# Tester.net
KiCad netlist of a schematic drawn in EAGLE
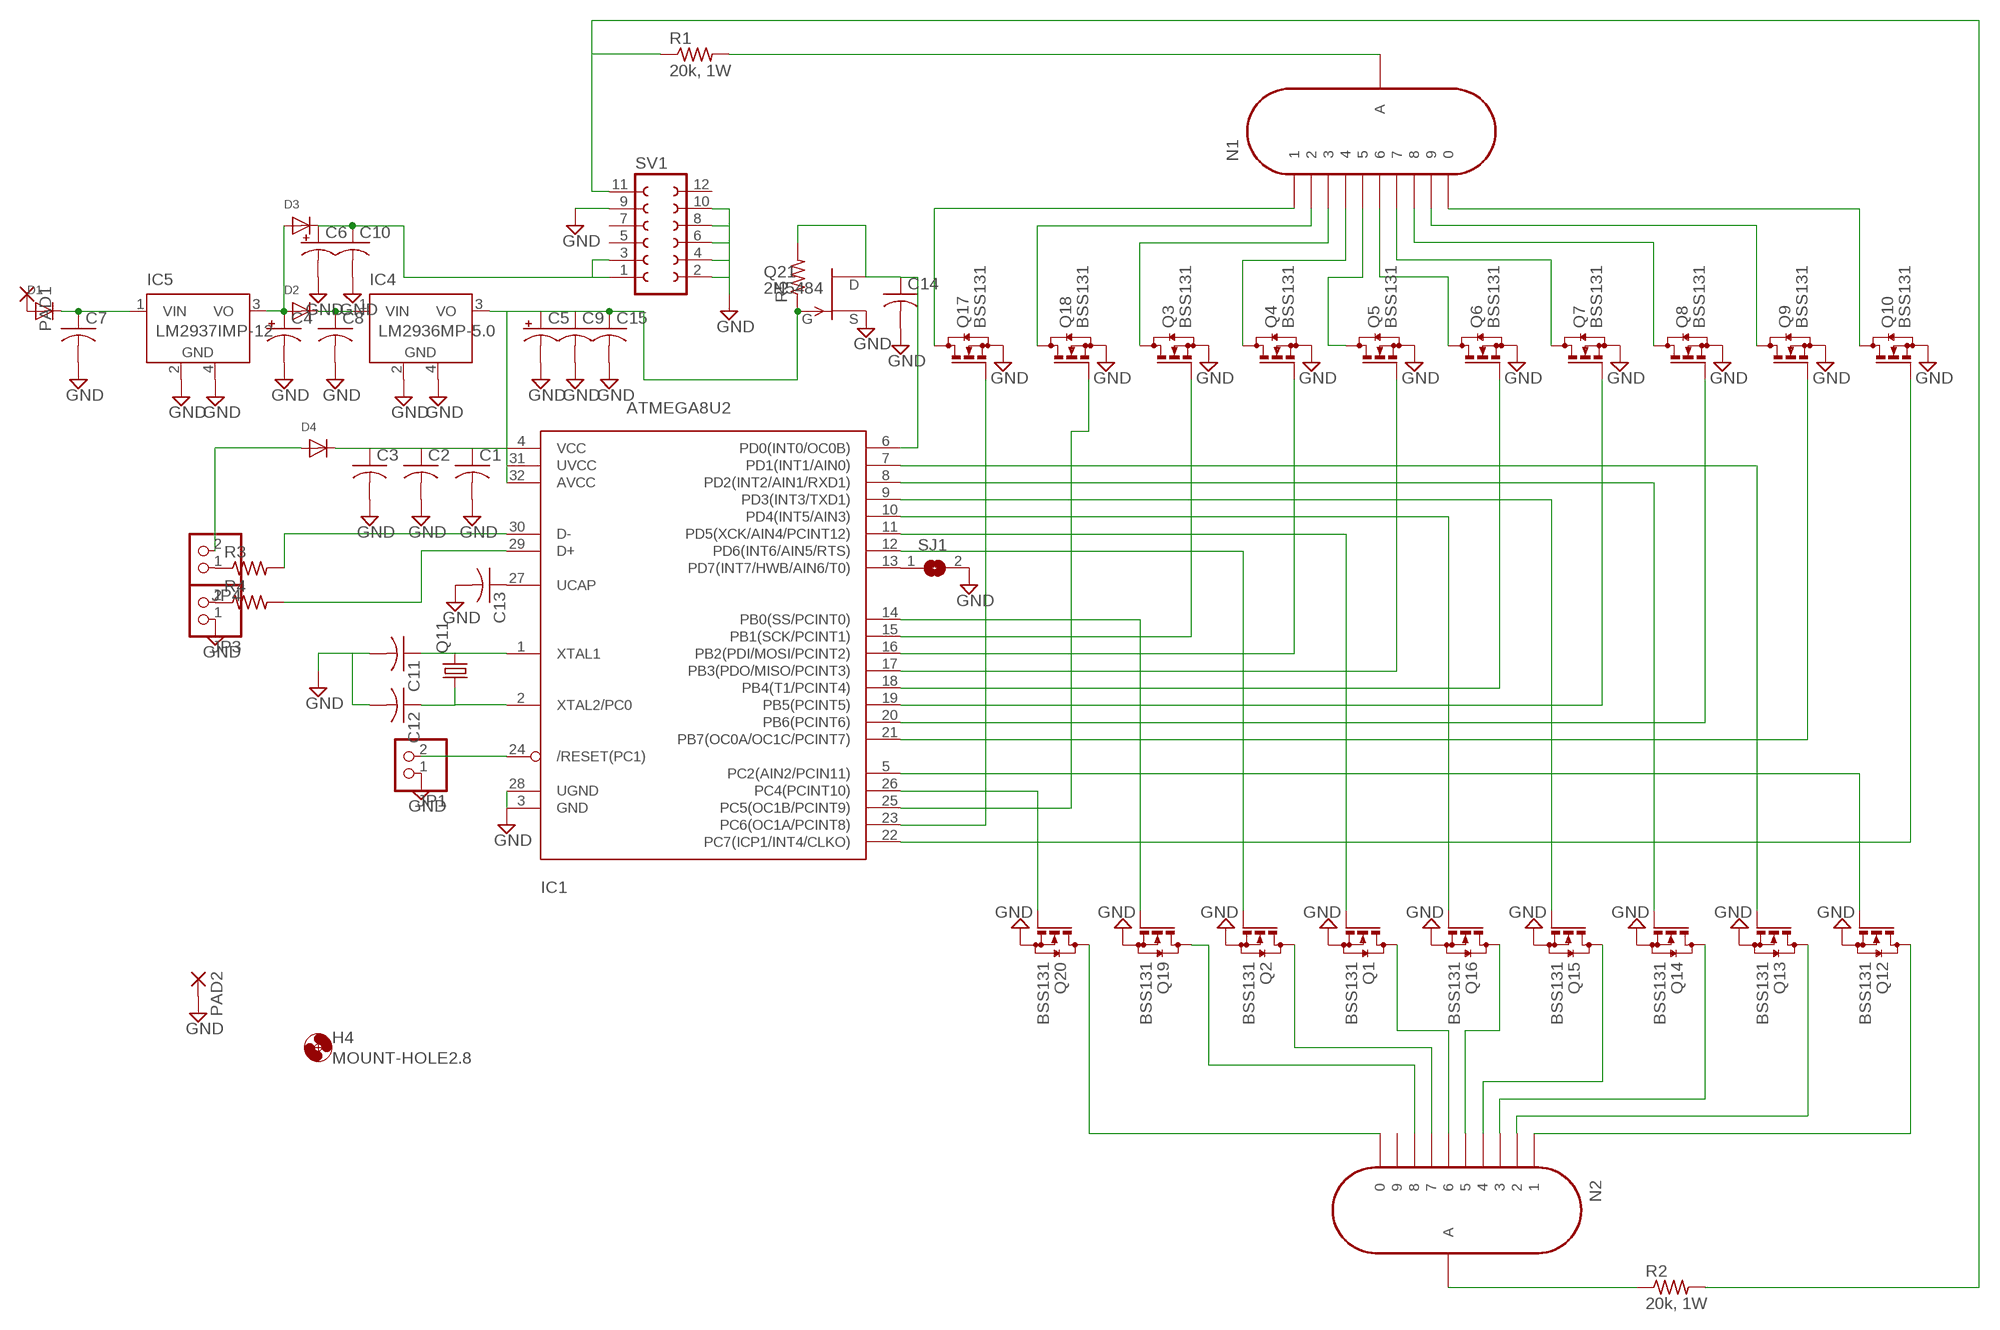
[diagram p0: schematic, sheet 1]

(export (version "E")
  (design (tool "Eeschema 10.0.6"))
  (components
    (comp (ref "C1")
      (value "C-USC0603K")
      (footprint "eagle-import:C0603K")
      (libsource (lib "eagle-import") (part "C-USC0603K"))
    )
    (comp (ref "C2")
      (value "C-USC0603K")
      (footprint "eagle-import:C0603K")
      (libsource (lib "eagle-import") (part "C-USC0603K"))
    )
    (comp (ref "C3")
      (value "C-USC0603K")
      (footprint "eagle-import:C0603K")
      (libsource (lib "eagle-import") (part "C-USC0603K"))
    )
    (comp (ref "C4")
      (value "CPOL-USE3.5-8")
      (footprint "eagle-import:E3,5-8")
      (libsource (lib "eagle-import") (part "CPOL-USE3.5-8"))
    )
    (comp (ref "C5")
      (value "CPOL-USE3.5-8")
      (footprint "eagle-import:E3,5-8")
      (libsource (lib "eagle-import") (part "CPOL-USE3.5-8"))
    )
    (comp (ref "C6")
      (value "CPOL-USE3.5-8")
      (footprint "eagle-import:E3,5-8")
      (libsource (lib "eagle-import") (part "CPOL-USE3.5-8"))
    )
    (comp (ref "C7")
      (value "C-USC1206K")
      (footprint "eagle-import:C1206K")
      (libsource (lib "eagle-import") (part "C-USC1206K"))
    )
    (comp (ref "C8")
      (value "C-USC1206K")
      (footprint "eagle-import:C1206K")
      (libsource (lib "eagle-import") (part "C-USC1206K"))
    )
    (comp (ref "C9")
      (value "C-USC1206K")
      (footprint "eagle-import:C1206K")
      (libsource (lib "eagle-import") (part "C-USC1206K"))
    )
    (comp (ref "C10")
      (value "C-USC1206K")
      (footprint "eagle-import:C1206K")
      (libsource (lib "eagle-import") (part "C-USC1206K"))
    )
    (comp (ref "C11")
      (value "C-USC1206K")
      (footprint "eagle-import:C1206K")
      (libsource (lib "eagle-import") (part "C-USC1206K"))
    )
    (comp (ref "C12")
      (value "C-USC1206K")
      (footprint "eagle-import:C1206K")
      (libsource (lib "eagle-import") (part "C-USC1206K"))
    )
    (comp (ref "C13")
      (value "C-USC1206K")
      (footprint "eagle-import:C1206K")
      (libsource (lib "eagle-import") (part "C-USC1206K"))
    )
    (comp (ref "C14")
      (value "C-USC1206K")
      (footprint "eagle-import:C1206K")
      (libsource (lib "eagle-import") (part "C-USC1206K"))
    )
    (comp (ref "C15")
      (value "C-USC1206K")
      (footprint "eagle-import:C1206K")
      (libsource (lib "eagle-import") (part "C-USC1206K"))
    )
    (comp (ref "D1")
      (value "DIODESMA")
      (footprint "eagle-import:SMADIODE")
      (libsource (lib "eagle-import") (part "DIODESMA"))
    )
    (comp (ref "D2")
      (value "DIODESMA")
      (footprint "eagle-import:SMADIODE")
      (libsource (lib "eagle-import") (part "DIODESMA"))
    )
    (comp (ref "D3")
      (value "DIODESMA")
      (footprint "eagle-import:SMADIODE")
      (libsource (lib "eagle-import") (part "DIODESMA"))
    )
    (comp (ref "D4")
      (value "DIODESOD-123")
      (footprint "eagle-import:SOD-123")
      (libsource (lib "eagle-import") (part "DIODESOD-123"))
    )
    (comp (ref "H4")
      (value "MOUNT-HOLE2.8")
      (footprint "eagle-import:2,8")
      (libsource (lib "eagle-import") (part "MOUNT-HOLE2.8"))
    )
    (comp (ref "IC1")
      (value "ATMEGA8U2")
      (footprint "eagle-import:TQFP32-08")
      (libsource (lib "eagle-import") (part "ATMEGA32U2-TQFP"))
    )
    (comp (ref "IC4")
      (value "LM2936MP-5.0")
      (footprint "eagle-import:SOT223")
      (fields (field (name "MF") "NATIONAL SEMICONDUCTOR") (field (name "MPN") "LM2936MP-5.0/NOPB"))
      (libsource (lib "eagle-import") (part "LM2936MP?-5.0"))
    )
    (comp (ref "IC5")
      (value "LM2937IMP-12")
      (footprint "eagle-import:SOT223")
      (fields (field (name "MF") "NATIONAL SEMICONDUCTOR") (field (name "MPN") "LM2936MP-5.0/NOPB"))
      (libsource (lib "eagle-import") (part "LM2936MP?-5.0"))
    )
    (comp (ref "JP1")
      (value "PINHD-1X2")
      (footprint "eagle-import:1X02")
      (libsource (lib "eagle-import") (part "PINHD-1X2"))
    )
    (comp (ref "JP3")
      (value "PINHD-1X2")
      (footprint "eagle-import:1X02")
      (libsource (lib "eagle-import") (part "PINHD-1X2"))
    )
    (comp (ref "JP4")
      (value "PINHD-1X2")
      (footprint "eagle-import:1X02")
      (libsource (lib "eagle-import") (part "PINHD-1X2"))
    )
    (comp (ref "N1")
      (value "IN-12A")
      (footprint "eagle-import:IN-12")
      (libsource (lib "eagle-import") (part "IN-12A"))
    )
    (comp (ref "N2")
      (value "IN-12A")
      (footprint "eagle-import:IN-12")
      (libsource (lib "eagle-import") (part "IN-12A"))
    )
    (comp (ref "PAD1")
      (value "3,81/1,4")
      (footprint "eagle-import:3,81_1,4")
      (libsource (lib "eagle-import") (part "3,81/1,4"))
    )
    (comp (ref "PAD2")
      (value "3,81/1,4")
      (footprint "eagle-import:3,81_1,4")
      (libsource (lib "eagle-import") (part "3,81/1,4"))
    )
    (comp (ref "Q1")
      (value "BSS131")
      (footprint "eagle-import:SOT23")
      (libsource (lib "eagle-import") (part "BSS123"))
    )
    (comp (ref "Q2")
      (value "BSS131")
      (footprint "eagle-import:SOT23")
      (libsource (lib "eagle-import") (part "BSS123"))
    )
    (comp (ref "Q3")
      (value "BSS131")
      (footprint "eagle-import:SOT23")
      (libsource (lib "eagle-import") (part "BSS123"))
    )
    (comp (ref "Q4")
      (value "BSS131")
      (footprint "eagle-import:SOT23")
      (libsource (lib "eagle-import") (part "BSS123"))
    )
    (comp (ref "Q5")
      (value "BSS131")
      (footprint "eagle-import:SOT23")
      (libsource (lib "eagle-import") (part "BSS123"))
    )
    (comp (ref "Q6")
      (value "BSS131")
      (footprint "eagle-import:SOT23")
      (libsource (lib "eagle-import") (part "BSS123"))
    )
    (comp (ref "Q7")
      (value "BSS131")
      (footprint "eagle-import:SOT23")
      (libsource (lib "eagle-import") (part "BSS123"))
    )
    (comp (ref "Q8")
      (value "BSS131")
      (footprint "eagle-import:SOT23")
      (libsource (lib "eagle-import") (part "BSS123"))
    )
    (comp (ref "Q9")
      (value "BSS131")
      (footprint "eagle-import:SOT23")
      (libsource (lib "eagle-import") (part "BSS123"))
    )
    (comp (ref "Q10")
      (value "BSS131")
      (footprint "eagle-import:SOT23")
      (libsource (lib "eagle-import") (part "BSS123"))
    )
    (comp (ref "Q11")
      (value "CRYSTALHC49S")
      (footprint "eagle-import:HC49_S")
      (libsource (lib "eagle-import") (part "CRYSTALHC49S"))
    )
    (comp (ref "Q12")
      (value "BSS131")
      (footprint "eagle-import:SOT23")
      (libsource (lib "eagle-import") (part "BSS123"))
    )
    (comp (ref "Q13")
      (value "BSS131")
      (footprint "eagle-import:SOT23")
      (libsource (lib "eagle-import") (part "BSS123"))
    )
    (comp (ref "Q14")
      (value "BSS131")
      (footprint "eagle-import:SOT23")
      (libsource (lib "eagle-import") (part "BSS123"))
    )
    (comp (ref "Q15")
      (value "BSS131")
      (footprint "eagle-import:SOT23")
      (libsource (lib "eagle-import") (part "BSS123"))
    )
    (comp (ref "Q16")
      (value "BSS131")
      (footprint "eagle-import:SOT23")
      (libsource (lib "eagle-import") (part "BSS123"))
    )
    (comp (ref "Q17")
      (value "BSS131")
      (footprint "eagle-import:SOT23")
      (libsource (lib "eagle-import") (part "BSS123"))
    )
    (comp (ref "Q18")
      (value "BSS131")
      (footprint "eagle-import:SOT23")
      (libsource (lib "eagle-import") (part "BSS123"))
    )
    (comp (ref "Q19")
      (value "BSS131")
      (footprint "eagle-import:SOT23")
      (libsource (lib "eagle-import") (part "BSS123"))
    )
    (comp (ref "Q20")
      (value "BSS131")
      (footprint "eagle-import:SOT23")
      (libsource (lib "eagle-import") (part "BSS123"))
    )
    (comp (ref "Q21")
      (value "2N5484")
      (footprint "eagle-import:TO92-")
      (libsource (lib "eagle-import") (part "?5482N4"))
    )
    (comp (ref "R1")
      (value "20k, 1W")
      (footprint "eagle-import:0309_12")
      (libsource (lib "eagle-import") (part "resistor_R-US_0309/12"))
    )
    (comp (ref "R2")
      (value "20k, 1W")
      (footprint "eagle-import:0309V")
      (libsource (lib "eagle-import") (part "resistor_R-US_0309/V"))
    )
    (comp (ref "R3")
      (value "R-US_R0805")
      (footprint "eagle-import:R0805")
      (libsource (lib "eagle-import") (part "R-US_R0805"))
    )
    (comp (ref "R4")
      (value "R-US_R0805")
      (footprint "eagle-import:R0805")
      (libsource (lib "eagle-import") (part "R-US_R0805"))
    )
    (comp (ref "R5")
      (value "R-US_R0805")
      (footprint "eagle-import:R0805")
      (libsource (lib "eagle-import") (part "R-US_R0805"))
    )
    (comp (ref "SJ1") (value "SJ") (footprint "eagle-import:SJ") (libsource (lib "eagle-import") (part "SJ")))
    (comp (ref "SV1")
      (value "FE06-2")
      (footprint "eagle-import:FE06-2")
      (libsource (lib "eagle-import") (part "FE06-2"))
    )
  )
  (nets
    (net (code "1") (name "GND") (class "Default")
      (node (ref "C1") (pin "2") (pinfunction "2_2") (pintype "passive"))
      (node (ref "C10") (pin "2") (pinfunction "2_2") (pintype "passive"))
      (node (ref "C11") (pin "2") (pinfunction "2_2") (pintype "passive"))
      (node (ref "C12") (pin "2") (pinfunction "2_2") (pintype "passive"))
      (node (ref "C13") (pin "2") (pinfunction "2_2") (pintype "passive"))
      (node (ref "C14") (pin "2") (pinfunction "2_2") (pintype "passive"))
      (node (ref "C15") (pin "2") (pinfunction "2_2") (pintype "passive"))
      (node (ref "C2") (pin "2") (pinfunction "2_2") (pintype "passive"))
      (node (ref "C3") (pin "2") (pinfunction "2_2") (pintype "passive"))
      (node (ref "C4") (pin "-") (pinfunction "-_-") (pintype "passive"))
      (node (ref "C5") (pin "-") (pinfunction "-_-") (pintype "passive"))
      (node (ref "C6") (pin "-") (pinfunction "-_-") (pintype "passive"))
      (node (ref "C7") (pin "2") (pinfunction "2_2") (pintype "passive"))
      (node (ref "C8") (pin "2") (pinfunction "2_2") (pintype "passive"))
      (node (ref "C9") (pin "2") (pinfunction "2_2") (pintype "passive"))
      (node (ref "IC1") (pin "28") (pinfunction "UGND_28") (pintype "bidirectional"))
      (node (ref "IC1") (pin "3") (pinfunction "GND_3") (pintype "bidirectional"))
      (node (ref "IC4") (pin "2") (pinfunction "GND_2") (pintype "passive"))
      (node (ref "IC4") (pin "4") (pinfunction "GND_4") (pintype "passive"))
      (node (ref "IC5") (pin "2") (pinfunction "GND_2") (pintype "passive"))
      (node (ref "IC5") (pin "4") (pinfunction "GND_4") (pintype "passive"))
      (node (ref "JP1") (pin "1") (pinfunction "1_1") (pintype "passive"))
      (node (ref "JP3") (pin "1") (pinfunction "1_1") (pintype "passive"))
      (node (ref "PAD2") (pin "1") (pinfunction "P_1") (pintype "passive"))
      (node (ref "Q1") (pin "2") (pinfunction "S_2") (pintype "passive"))
      (node (ref "Q10") (pin "2") (pinfunction "S_2") (pintype "passive"))
      (node (ref "Q12") (pin "2") (pinfunction "S_2") (pintype "passive"))
      (node (ref "Q13") (pin "2") (pinfunction "S_2") (pintype "passive"))
      (node (ref "Q14") (pin "2") (pinfunction "S_2") (pintype "passive"))
      (node (ref "Q15") (pin "2") (pinfunction "S_2") (pintype "passive"))
      (node (ref "Q16") (pin "2") (pinfunction "S_2") (pintype "passive"))
      (node (ref "Q17") (pin "2") (pinfunction "S_2") (pintype "passive"))
      (node (ref "Q18") (pin "2") (pinfunction "S_2") (pintype "passive"))
      (node (ref "Q19") (pin "2") (pinfunction "S_2") (pintype "passive"))
      (node (ref "Q2") (pin "2") (pinfunction "S_2") (pintype "passive"))
      (node (ref "Q20") (pin "2") (pinfunction "S_2") (pintype "passive"))
      (node (ref "Q21") (pin "2") (pinfunction "S_2") (pintype "passive"))
      (node (ref "Q3") (pin "2") (pinfunction "S_2") (pintype "passive"))
      (node (ref "Q4") (pin "2") (pinfunction "S_2") (pintype "passive"))
      (node (ref "Q5") (pin "2") (pinfunction "S_2") (pintype "passive"))
      (node (ref "Q6") (pin "2") (pinfunction "S_2") (pintype "passive"))
      (node (ref "Q7") (pin "2") (pinfunction "S_2") (pintype "passive"))
      (node (ref "Q8") (pin "2") (pinfunction "S_2") (pintype "passive"))
      (node (ref "Q9") (pin "2") (pinfunction "S_2") (pintype "passive"))
      (node (ref "SJ1") (pin "2") (pinfunction "2_2") (pintype "passive"))
      (node (ref "SV1") (pin "10") (pinfunction "10_10") (pintype "passive"))
      (node (ref "SV1") (pin "2") (pinfunction "2_2") (pintype "passive"))
      (node (ref "SV1") (pin "4") (pinfunction "4_4") (pintype "passive"))
      (node (ref "SV1") (pin "6") (pinfunction "6_6") (pintype "passive"))
      (node (ref "SV1") (pin "8") (pinfunction "8_8") (pintype "passive"))
      (node (ref "SV1") (pin "9") (pinfunction "9_9") (pintype "passive"))
    )
    (net (code "2") (name "Net-(C10-Pad1)") (class "Default")
      (node (ref "C10") (pin "1") (pinfunction "1_1") (pintype "passive"))
      (node (ref "C6") (pin "+") (pinfunction "+_+") (pintype "passive"))
      (node (ref "D3") (pin "C") (pinfunction "C_C") (pintype "passive"))
      (node (ref "SV1") (pin "1") (pinfunction "1_1") (pintype "passive"))
      (node (ref "SV1") (pin "3") (pinfunction "3_3") (pintype "passive"))
    )
    (net (code "3") (name "Net-(D4-PadA)") (class "Default")
      (node (ref "D4") (pin "A") (pinfunction "A_A") (pintype "passive"))
      (node (ref "JP4") (pin "2") (pinfunction "2_2") (pintype "passive"))
    )
    (net (code "4") (name "Net-(IC1-AVCC)") (class "Default")
      (node (ref "C1") (pin "1") (pinfunction "1_1") (pintype "passive"))
      (node (ref "C15") (pin "1") (pinfunction "1_1") (pintype "passive"))
      (node (ref "C2") (pin "1") (pinfunction "1_1") (pintype "passive"))
      (node (ref "C3") (pin "1") (pinfunction "1_1") (pintype "passive"))
      (node (ref "C5") (pin "+") (pinfunction "+_+") (pintype "passive"))
      (node (ref "C9") (pin "1") (pinfunction "1_1") (pintype "passive"))
      (node (ref "D4") (pin "C") (pinfunction "C_C") (pintype "passive"))
      (node (ref "IC1") (pin "31") (pinfunction "UVCC_31") (pintype "bidirectional"))
      (node (ref "IC1") (pin "32") (pinfunction "AVCC_32") (pintype "bidirectional"))
      (node (ref "IC1") (pin "4") (pinfunction "VCC_4") (pintype "bidirectional"))
      (node (ref "IC4") (pin "3") (pinfunction "VO_3") (pintype "passive"))
      (node (ref "Q21") (pin "1") (pinfunction "G_1") (pintype "passive"))
      (node (ref "R5") (pin "1") (pinfunction "1_1") (pintype "passive"))
    )
    (net (code "5") (name "Net-(IC1-D+)") (class "Default")
      (node (ref "IC1") (pin "29") (pinfunction "D+_29") (pintype "bidirectional"))
      (node (ref "R4") (pin "2") (pinfunction "2_2") (pintype "passive"))
    )
    (net (code "6") (name "Net-(IC1-D-)") (class "Default")
      (node (ref "IC1") (pin "30") (pinfunction "D-_30") (pintype "bidirectional"))
      (node (ref "R3") (pin "2") (pinfunction "2_2") (pintype "passive"))
    )
    (net (code "7") (name "Net-(IC1-PB0(SS{slash}PCINT0))") (class "Default")
      (node (ref "IC1") (pin "14") (pinfunction "PB0(SS/PCINT0)_14") (pintype "bidirectional"))
      (node (ref "Q19") (pin "1") (pinfunction "G_1") (pintype "passive"))
    )
    (net (code "8") (name "Net-(IC1-PB1(SCK{slash}PCINT1))") (class "Default")
      (node (ref "IC1") (pin "15") (pinfunction "PB1(SCK/PCINT1)_15") (pintype "bidirectional"))
      (node (ref "Q3") (pin "1") (pinfunction "G_1") (pintype "passive"))
    )
    (net (code "9") (name "Net-(IC1-PB2(PDI{slash}MOSI{slash}PCINT2))") (class "Default")
      (node (ref "IC1") (pin "16") (pinfunction "PB2(PDI/MOSI/PCINT2)_16") (pintype "bidirectional"))
      (node (ref "Q4") (pin "1") (pinfunction "G_1") (pintype "passive"))
    )
    (net (code "10") (name "Net-(IC1-PB3(PDO{slash}MISO{slash}PCINT3))") (class "Default")
      (node (ref "IC1") (pin "17") (pinfunction "PB3(PDO/MISO/PCINT3)_17") (pintype "bidirectional"))
      (node (ref "Q5") (pin "1") (pinfunction "G_1") (pintype "passive"))
    )
    (net (code "11") (name "Net-(IC1-PB4(T1{slash}PCINT4))") (class "Default")
      (node (ref "IC1") (pin "18") (pinfunction "PB4(T1/PCINT4)_18") (pintype "bidirectional"))
      (node (ref "Q6") (pin "1") (pinfunction "G_1") (pintype "passive"))
    )
    (net (code "12") (name "Net-(IC1-PB5(PCINT5))") (class "Default")
      (node (ref "IC1") (pin "19") (pinfunction "PB5(PCINT5)_19") (pintype "bidirectional"))
      (node (ref "Q7") (pin "1") (pinfunction "G_1") (pintype "passive"))
    )
    (net (code "13") (name "Net-(IC1-PB6(PCINT6))") (class "Default")
      (node (ref "IC1") (pin "20") (pinfunction "PB6(PCINT6)_20") (pintype "bidirectional"))
      (node (ref "Q8") (pin "1") (pinfunction "G_1") (pintype "passive"))
    )
    (net (code "14") (name "Net-(IC1-PB7(OC0A{slash}OC1C{slash}PCINT7))") (class "Default")
      (node (ref "IC1") (pin "21") (pinfunction "PB7(OC0A/OC1C/PCINT7)_21") (pintype "bidirectional"))
      (node (ref "Q9") (pin "1") (pinfunction "G_1") (pintype "passive"))
    )
    (net (code "15") (name "Net-(IC1-PC2(AIN2{slash}PCIN11))") (class "Default")
      (node (ref "IC1") (pin "5") (pinfunction "PC2(AIN2/PCIN11)_5") (pintype "bidirectional"))
      (node (ref "Q12") (pin "1") (pinfunction "G_1") (pintype "passive"))
    )
    (net (code "16") (name "Net-(IC1-PC4(PCINT10))") (class "Default")
      (node (ref "IC1") (pin "26") (pinfunction "PC4(PCINT10)_26") (pintype "bidirectional"))
      (node (ref "Q20") (pin "1") (pinfunction "G_1") (pintype "passive"))
    )
    (net (code "17") (name "Net-(IC1-PC5(OC1B{slash}PCINT9))") (class "Default")
      (node (ref "IC1") (pin "25") (pinfunction "PC5(OC1B/PCINT9)_25") (pintype "bidirectional"))
      (node (ref "Q18") (pin "1") (pinfunction "G_1") (pintype "passive"))
    )
    (net (code "18") (name "Net-(IC1-PC6(OC1A{slash}PCINT8))") (class "Default")
      (node (ref "IC1") (pin "23") (pinfunction "PC6(OC1A/PCINT8)_23") (pintype "bidirectional"))
      (node (ref "Q17") (pin "1") (pinfunction "G_1") (pintype "passive"))
    )
    (net (code "19") (name "Net-(IC1-PC7(ICP1{slash}INT4{slash}CLKO))") (class "Default")
      (node (ref "IC1") (pin "22") (pinfunction "PC7(ICP1/INT4/CLKO)_22") (pintype "bidirectional"))
      (node (ref "Q10") (pin "1") (pinfunction "G_1") (pintype "passive"))
    )
    (net (code "20") (name "Net-(IC1-PD0(INT0{slash}OC0B))") (class "Default")
      (node (ref "C14") (pin "1") (pinfunction "1_1") (pintype "passive"))
      (node (ref "IC1") (pin "6") (pinfunction "PD0(INT0/OC0B)_6") (pintype "bidirectional"))
      (node (ref "Q21") (pin "3") (pinfunction "D_3") (pintype "passive"))
      (node (ref "R5") (pin "2") (pinfunction "2_2") (pintype "passive"))
    )
    (net (code "21") (name "Net-(IC1-PD1(INT1{slash}AIN0))") (class "Default")
      (node (ref "IC1") (pin "7") (pinfunction "PD1(INT1/AIN0)_7") (pintype "bidirectional"))
      (node (ref "Q13") (pin "1") (pinfunction "G_1") (pintype "passive"))
    )
    (net (code "22") (name "Net-(IC1-PD2(INT2{slash}AIN1{slash}RXD1))") (class "Default")
      (node (ref "IC1") (pin "8") (pinfunction "PD2(INT2/AIN1/RXD1)_8") (pintype "bidirectional"))
      (node (ref "Q14") (pin "1") (pinfunction "G_1") (pintype "passive"))
    )
    (net (code "23") (name "Net-(IC1-PD3(INT3{slash}TXD1))") (class "Default")
      (node (ref "IC1") (pin "9") (pinfunction "PD3(INT3/TXD1)_9") (pintype "bidirectional"))
      (node (ref "Q15") (pin "1") (pinfunction "G_1") (pintype "passive"))
    )
    (net (code "24") (name "Net-(IC1-PD4(INT5{slash}AIN3))") (class "Default")
      (node (ref "IC1") (pin "10") (pinfunction "PD4(INT5/AIN3)_10") (pintype "bidirectional"))
      (node (ref "Q16") (pin "1") (pinfunction "G_1") (pintype "passive"))
    )
    (net (code "25") (name "Net-(IC1-PD5(XCK{slash}AIN4{slash}PCINT12))") (class "Default")
      (node (ref "IC1") (pin "11") (pinfunction "PD5(XCK/AIN4/PCINT12)_11") (pintype "bidirectional"))
      (node (ref "Q1") (pin "1") (pinfunction "G_1") (pintype "passive"))
    )
    (net (code "26") (name "Net-(IC1-PD6(INT6{slash}AIN5{slash}RTS))") (class "Default")
      (node (ref "IC1") (pin "12") (pinfunction "PD6(INT6/AIN5/RTS)_12") (pintype "bidirectional"))
      (node (ref "Q2") (pin "1") (pinfunction "G_1") (pintype "passive"))
    )
    (net (code "27") (name "Net-(IC1-PD7(INT7{slash}HWB{slash}AIN6{slash}T0))") (class "Default")
      (node (ref "IC1") (pin "13") (pinfunction "PD7(INT7/HWB/AIN6/T0)_13") (pintype "bidirectional"))
      (node (ref "SJ1") (pin "1") (pinfunction "1_1") (pintype "passive"))
    )
    (net (code "28") (name "Net-(IC1-UCAP)") (class "Default")
      (node (ref "C13") (pin "1") (pinfunction "1_1") (pintype "passive"))
      (node (ref "IC1") (pin "27") (pinfunction "UCAP_27") (pintype "bidirectional"))
    )
    (net (code "29") (name "Net-(IC1-XTAL1)") (class "Default")
      (node (ref "C11") (pin "1") (pinfunction "1_1") (pintype "passive"))
      (node (ref "IC1") (pin "1") (pinfunction "XTAL1_1") (pintype "bidirectional"))
      (node (ref "Q11") (pin "2") (pinfunction "2_2") (pintype "passive"))
    )
    (net (code "30") (name "Net-(IC1-XTAL2{slash}PC0)") (class "Default")
      (node (ref "C12") (pin "1") (pinfunction "1_1") (pintype "passive"))
      (node (ref "IC1") (pin "2") (pinfunction "XTAL2/PC0_2") (pintype "bidirectional"))
      (node (ref "Q11") (pin "1") (pinfunction "1_1") (pintype "passive"))
    )
    (net (code "31") (name "Net-(IC1-{slash}RESET(PC1))") (class "Default")
      (node (ref "IC1") (pin "24") (pinfunction "/RESET(PC1)_24") (pintype "bidirectional"))
      (node (ref "JP1") (pin "2") (pinfunction "2_2") (pintype "passive"))
    )
    (net (code "32") (name "Net-(IC4-VIN)") (class "Default")
      (node (ref "C8") (pin "1") (pinfunction "1_1") (pintype "passive"))
      (node (ref "D2") (pin "C") (pinfunction "C_C") (pintype "passive"))
      (node (ref "IC4") (pin "1") (pinfunction "VIN_1") (pintype "input"))
    )
    (net (code "33") (name "Net-(IC5-VIN)") (class "Default")
      (node (ref "C7") (pin "1") (pinfunction "1_1") (pintype "passive"))
      (node (ref "D1") (pin "C") (pinfunction "C_C") (pintype "passive"))
      (node (ref "IC5") (pin "1") (pinfunction "VIN_1") (pintype "input"))
    )
    (net (code "34") (name "Net-(IC5-VO)") (class "Default")
      (node (ref "C4") (pin "+") (pinfunction "+_+") (pintype "passive"))
      (node (ref "D2") (pin "A") (pinfunction "A_A") (pintype "passive"))
      (node (ref "D3") (pin "A") (pinfunction "A_A") (pintype "passive"))
      (node (ref "IC5") (pin "3") (pinfunction "VO_3") (pintype "passive"))
    )
    (net (code "35") (name "Net-(JP3-Pad2)") (class "Default")
      (node (ref "JP3") (pin "2") (pinfunction "2_2") (pintype "passive"))
      (node (ref "R4") (pin "1") (pinfunction "1_1") (pintype "passive"))
    )
    (net (code "36") (name "Net-(JP4-Pad1)") (class "Default")
      (node (ref "JP4") (pin "1") (pinfunction "1_1") (pintype "passive"))
      (node (ref "R3") (pin "1") (pinfunction "1_1") (pintype "passive"))
    )
    (net (code "37") (name "Net-(N1-PadA)") (class "Default")
      (node (ref "N1") (pin "A") (pinfunction "A_A") (pintype "bidirectional"))
      (node (ref "R1") (pin "2") (pinfunction "2_2") (pintype "passive"))
    )
    (net (code "38") (name "Net-(N2-PadA)") (class "Default")
      (node (ref "N2") (pin "A") (pinfunction "A_A") (pintype "bidirectional"))
      (node (ref "R2") (pin "1") (pinfunction "1_1") (pintype "passive"))
    )
    (net (code "39") (name "Net-(PAD1-P)") (class "Default")
      (node (ref "D1") (pin "A") (pinfunction "A_A") (pintype "passive"))
      (node (ref "PAD1") (pin "1") (pinfunction "P_1") (pintype "passive"))
    )
    (net (code "40") (name "Net-(Q1-D)") (class "Default")
      (node (ref "N2") (pin "6") (pinfunction "6_6") (pintype "bidirectional"))
      (node (ref "Q1") (pin "3") (pinfunction "D_3") (pintype "passive"))
    )
    (net (code "41") (name "Net-(Q2-D)") (class "Default")
      (node (ref "N2") (pin "7") (pinfunction "7_7") (pintype "bidirectional"))
      (node (ref "Q2") (pin "3") (pinfunction "D_3") (pintype "passive"))
    )
    (net (code "42") (name "Net-(Q3-D)") (class "Default")
      (node (ref "N1") (pin "3") (pinfunction "3_3") (pintype "bidirectional"))
      (node (ref "Q3") (pin "3") (pinfunction "D_3") (pintype "passive"))
    )
    (net (code "43") (name "Net-(Q4-D)") (class "Default")
      (node (ref "N1") (pin "4") (pinfunction "4_4") (pintype "bidirectional"))
      (node (ref "Q4") (pin "3") (pinfunction "D_3") (pintype "passive"))
    )
    (net (code "44") (name "Net-(Q5-D)") (class "Default")
      (node (ref "N1") (pin "5") (pinfunction "5_5") (pintype "bidirectional"))
      (node (ref "Q5") (pin "3") (pinfunction "D_3") (pintype "passive"))
    )
    (net (code "45") (name "Net-(Q6-D)") (class "Default")
      (node (ref "N1") (pin "6") (pinfunction "6_6") (pintype "bidirectional"))
      (node (ref "Q6") (pin "3") (pinfunction "D_3") (pintype "passive"))
    )
    (net (code "46") (name "Net-(Q7-D)") (class "Default")
      (node (ref "N1") (pin "7") (pinfunction "7_7") (pintype "bidirectional"))
      (node (ref "Q7") (pin "3") (pinfunction "D_3") (pintype "passive"))
    )
    (net (code "47") (name "Net-(Q8-D)") (class "Default")
      (node (ref "N1") (pin "8") (pinfunction "8_8") (pintype "bidirectional"))
      (node (ref "Q8") (pin "3") (pinfunction "D_3") (pintype "passive"))
    )
    (net (code "48") (name "Net-(Q9-D)") (class "Default")
      (node (ref "N1") (pin "9") (pinfunction "9_9") (pintype "bidirectional"))
      (node (ref "Q9") (pin "3") (pinfunction "D_3") (pintype "passive"))
    )
    (net (code "49") (name "Net-(Q10-D)") (class "Default")
      (node (ref "N1") (pin "0") (pinfunction "0_0") (pintype "bidirectional"))
      (node (ref "Q10") (pin "3") (pinfunction "D_3") (pintype "passive"))
    )
    (net (code "50") (name "Net-(Q12-D)") (class "Default")
      (node (ref "N2") (pin "1") (pinfunction "1_1") (pintype "bidirectional"))
      (node (ref "Q12") (pin "3") (pinfunction "D_3") (pintype "passive"))
    )
    (net (code "51") (name "Net-(Q13-D)") (class "Default")
      (node (ref "N2") (pin "2") (pinfunction "2_2") (pintype "bidirectional"))
      (node (ref "Q13") (pin "3") (pinfunction "D_3") (pintype "passive"))
    )
    (net (code "52") (name "Net-(Q14-D)") (class "Default")
      (node (ref "N2") (pin "3") (pinfunction "3_3") (pintype "bidirectional"))
      (node (ref "Q14") (pin "3") (pinfunction "D_3") (pintype "passive"))
    )
    (net (code "53") (name "Net-(Q15-D)") (class "Default")
      (node (ref "N2") (pin "4") (pinfunction "4_4") (pintype "bidirectional"))
      (node (ref "Q15") (pin "3") (pinfunction "D_3") (pintype "passive"))
    )
    (net (code "54") (name "Net-(Q16-D)") (class "Default")
      (node (ref "N2") (pin "5") (pinfunction "5_5") (pintype "bidirectional"))
      (node (ref "Q16") (pin "3") (pinfunction "D_3") (pintype "passive"))
    )
    (net (code "55") (name "Net-(Q17-D)") (class "Default")
      (node (ref "N1") (pin "1") (pinfunction "1_1") (pintype "bidirectional"))
      (node (ref "Q17") (pin "3") (pinfunction "D_3") (pintype "passive"))
    )
    (net (code "56") (name "Net-(Q18-D)") (class "Default")
      (node (ref "N1") (pin "2") (pinfunction "2_2") (pintype "bidirectional"))
      (node (ref "Q18") (pin "3") (pinfunction "D_3") (pintype "passive"))
    )
    (net (code "57") (name "Net-(Q19-D)") (class "Default")
      (node (ref "N2") (pin "8") (pinfunction "8_8") (pintype "bidirectional"))
      (node (ref "Q19") (pin "3") (pinfunction "D_3") (pintype "passive"))
    )
    (net (code "58") (name "Net-(Q20-D)") (class "Default")
      (node (ref "N2") (pin "0") (pinfunction "0_0") (pintype "bidirectional"))
      (node (ref "Q20") (pin "3") (pinfunction "D_3") (pintype "passive"))
    )
    (net (code "59") (name "Net-(R1-Pad1)") (class "Default")
      (node (ref "R1") (pin "1") (pinfunction "1_1") (pintype "passive"))
      (node (ref "R2") (pin "2") (pinfunction "2_2") (pintype "passive"))
      (node (ref "SV1") (pin "11") (pinfunction "11_11") (pintype "passive"))
    )
    (net (code "60") (name "unconnected-(N2-Pad9)") (class "Default")
      (node (ref "N2") (pin "9") (pinfunction "9_9") (pintype "bidirectional"))
    )
    (net (code "61") (name "unconnected-(SV1-Pad5)") (class "Default")
      (node (ref "SV1") (pin "5") (pinfunction "5_5") (pintype "passive"))
    )
    (net (code "62") (name "unconnected-(SV1-Pad7)") (class "Default")
      (node (ref "SV1") (pin "7") (pinfunction "7_7") (pintype "passive"))
    )
    (net (code "63") (name "unconnected-(SV1-Pad12)") (class "Default")
      (node (ref "SV1") (pin "12") (pinfunction "12_12") (pintype "passive"))
    )
  )
)
